# Etta_and_Gella_diamond_dev.net
KiCad netlist of a schematic drawn in EAGLE
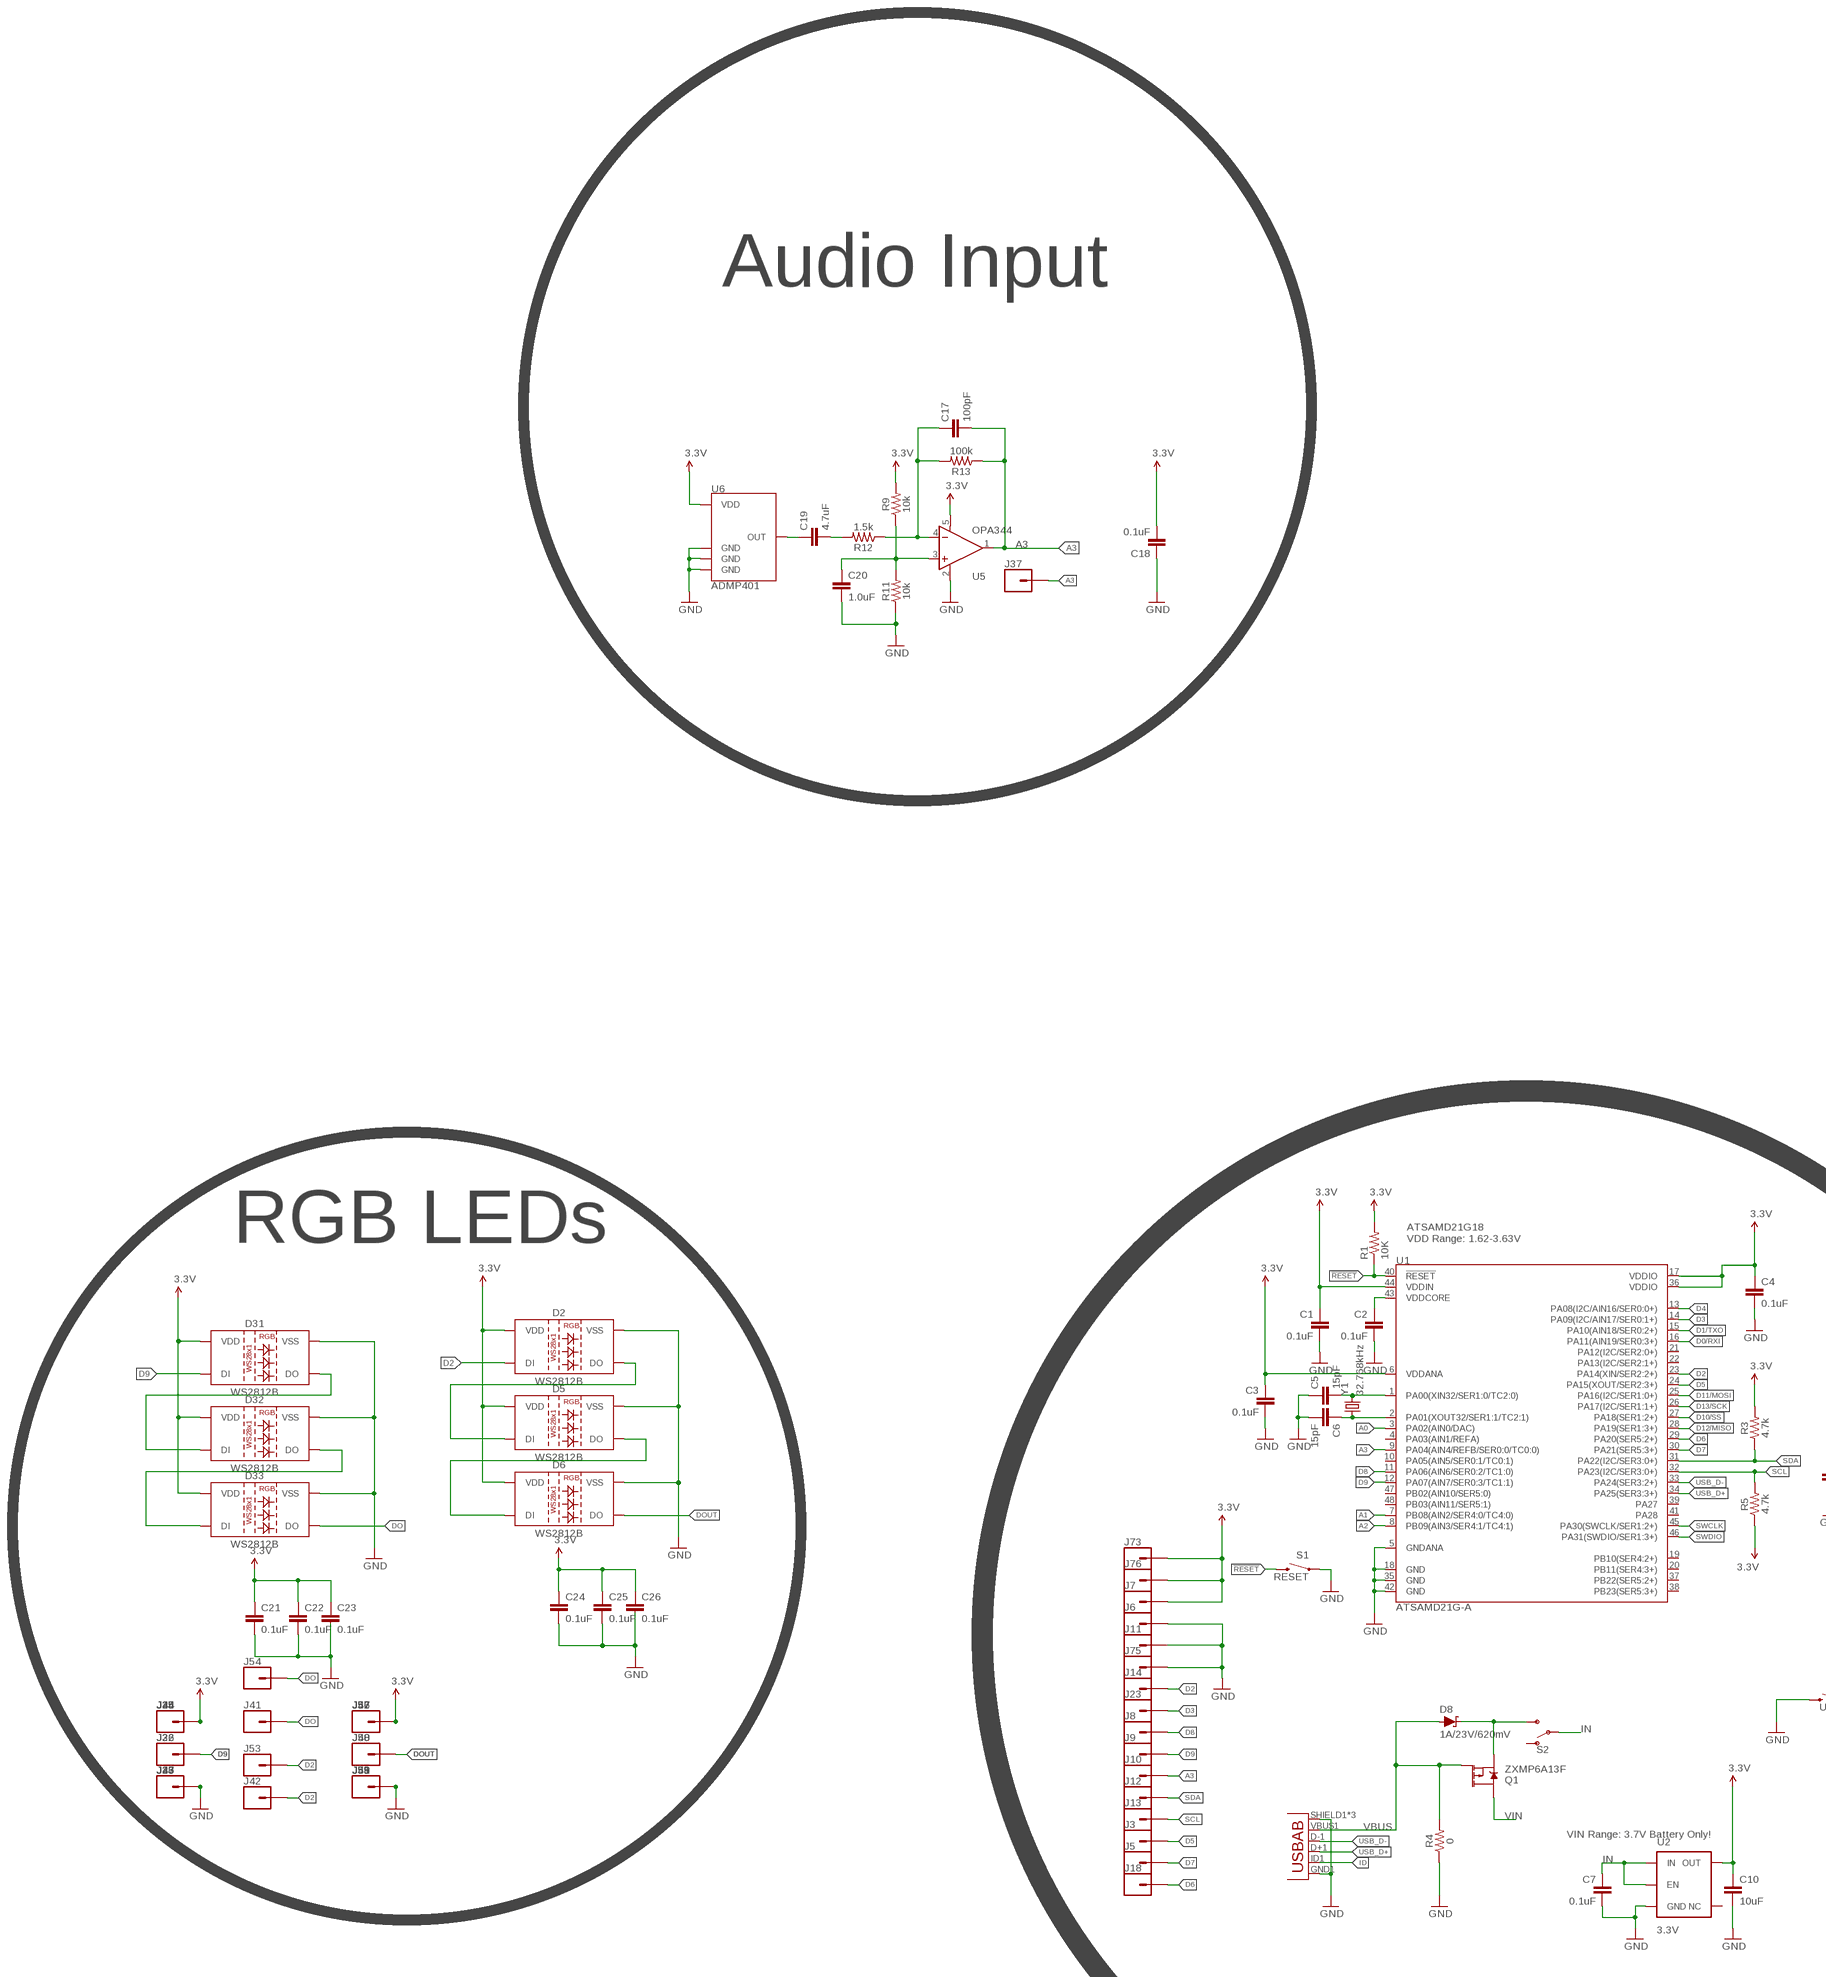
[diagram p0: schematic, sheet 1, part 1 of 3]
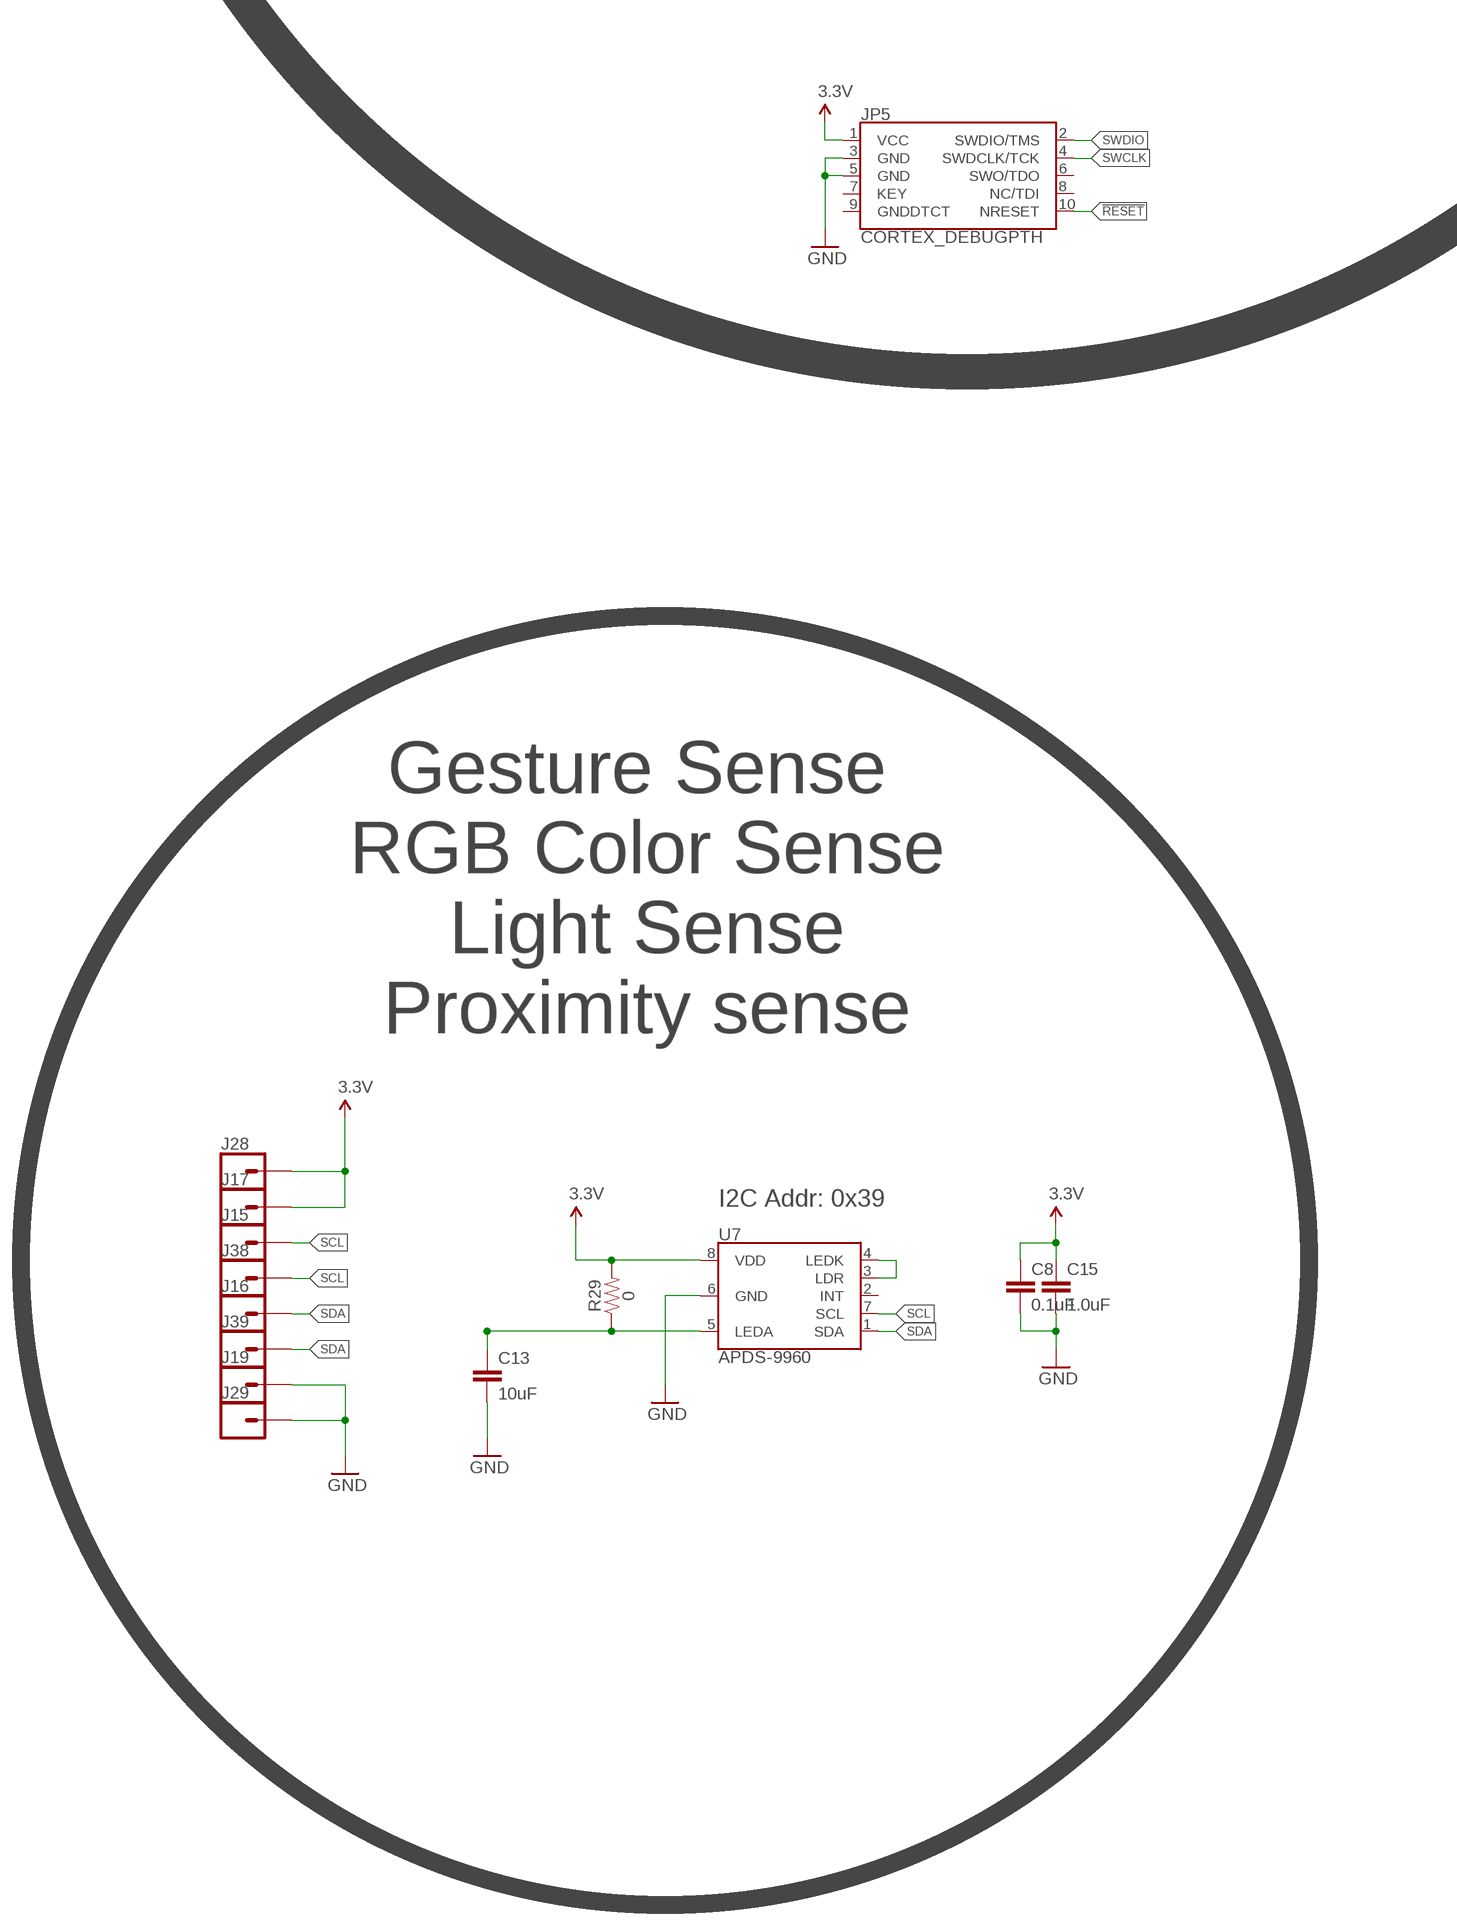
[diagram p1: schematic, sheet 1, part 2 of 3]
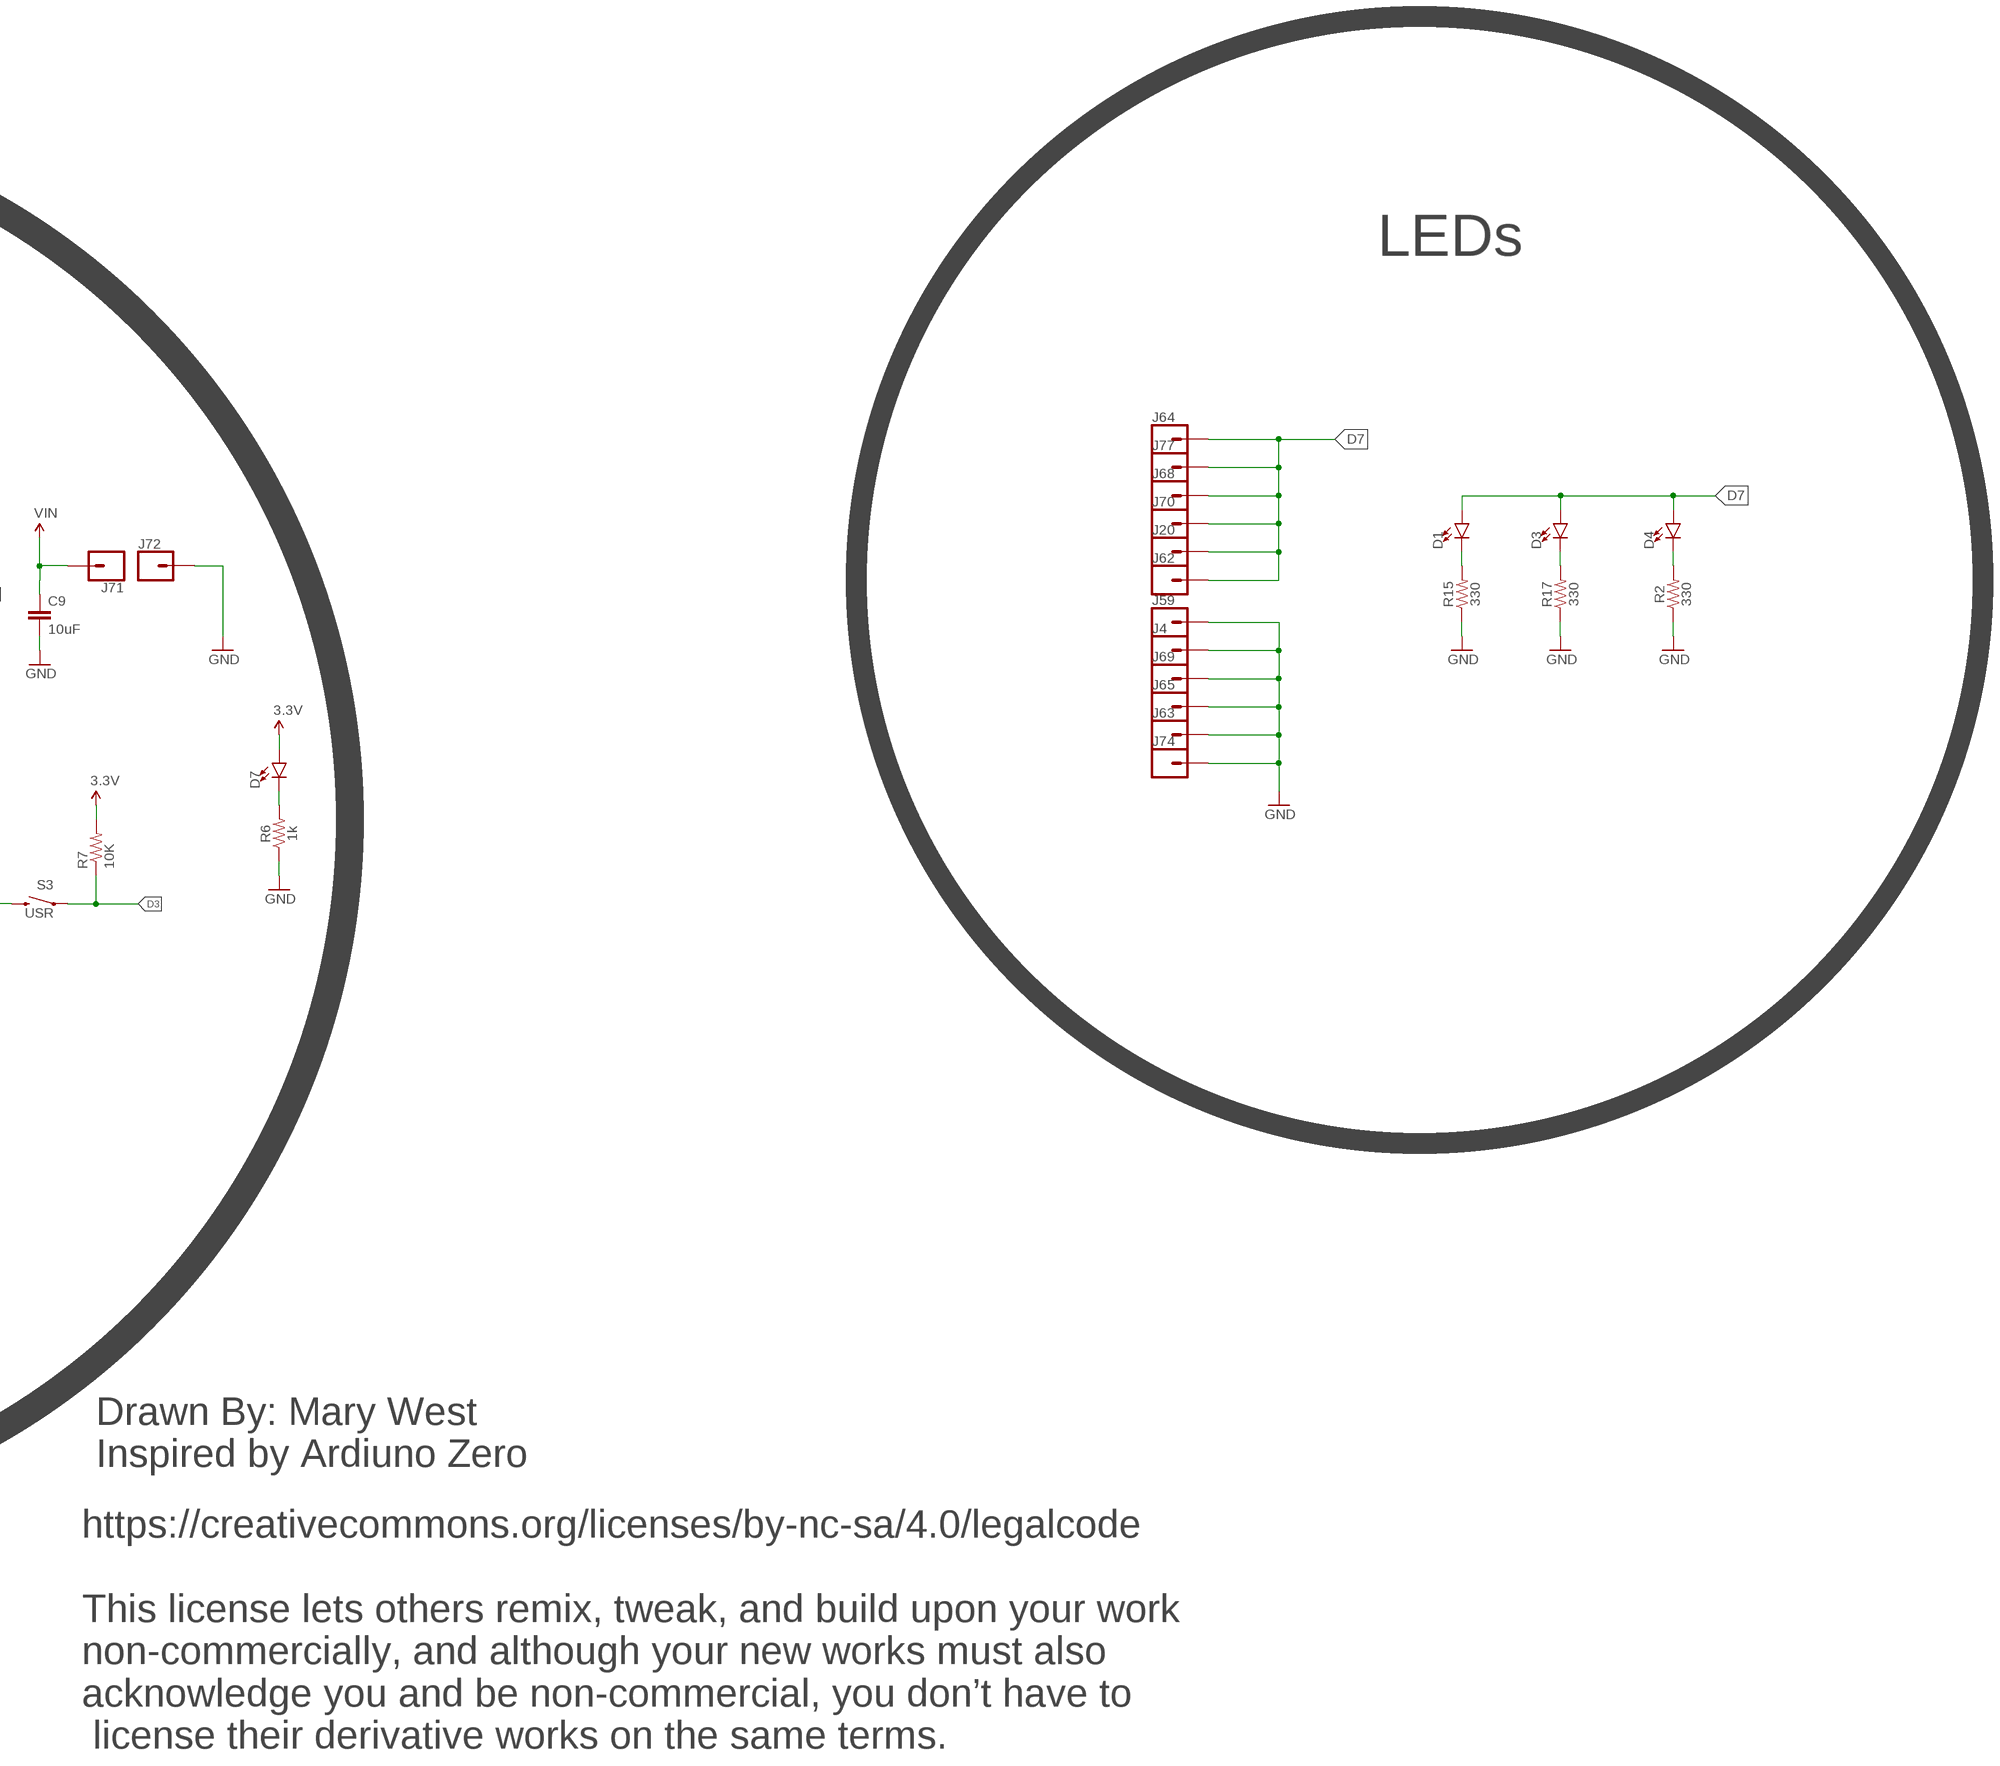
[diagram p2: schematic, sheet 1, part 3 of 3]

(export (version "E")
  (design (tool "Eeschema 10.0.6"))
  (components
    (comp (ref "C1")
      (value "0.1uF")
      (footprint "eagle-import:0603")
      (libsource (lib "eagle-import") (part "0.1UF-0603-25V-(+80/-20%)"))
    )
    (comp (ref "C2")
      (value "0.1uF")
      (footprint "eagle-import:0603")
      (libsource (lib "eagle-import") (part "0.1UF-0603-25V-(+80/-20%)"))
    )
    (comp (ref "C3")
      (value "0.1uF")
      (footprint "eagle-import:0603")
      (libsource (lib "eagle-import") (part "0.1UF-0603-25V-(+80/-20%)"))
    )
    (comp (ref "C4")
      (value "0.1uF")
      (footprint "eagle-import:0603")
      (libsource (lib "eagle-import") (part "0.1UF-0603-25V-(+80/-20%)"))
    )
    (comp (ref "C5")
      (value "15pF")
      (footprint "eagle-import:0603")
      (libsource (lib "eagle-import") (part "15PF-0603-50V-5%"))
    )
    (comp (ref "C6")
      (value "15pF")
      (footprint "eagle-import:0603")
      (libsource (lib "eagle-import") (part "15PF-0603-50V-5%"))
    )
    (comp (ref "C7")
      (value "0.1uF")
      (footprint "eagle-import:0603")
      (libsource (lib "eagle-import") (part "0.1UF-0603-25V-(+80/-20%)"))
    )
    (comp (ref "C8")
      (value "0.1uF")
      (footprint "eagle-import:0603")
      (libsource (lib "eagle-import") (part "0.1UF-0603-25V-(+80/-20%)"))
    )
    (comp (ref "C9")
      (value "10uF")
      (footprint "eagle-import:0603")
      (libsource (lib "eagle-import") (part "SparkFun-Capacitors_510_10UF-0603-6.3V-20%"))
    )
    (comp (ref "C10")
      (value "10uF")
      (footprint "eagle-import:0603")
      (libsource (lib "eagle-import") (part "SparkFun-Capacitors_510_10UF-0603-6.3V-20%"))
    )
    (comp (ref "C13")
      (value "10uF")
      (footprint "eagle-import:0805")
      (libsource (lib "eagle-import") (part "10UF-0805-10V-10%"))
    )
    (comp (ref "C15")
      (value "1.0uF")
      (footprint "eagle-import:0603")
      (libsource (lib "eagle-import") (part "1.0UF-0603-16V-10%"))
    )
    (comp (ref "C17")
      (value "100pF")
      (footprint "eagle-import:0603")
      (libsource (lib "eagle-import") (part "100PF-0603-50V-5%"))
    )
    (comp (ref "C18")
      (value "0.1uF")
      (footprint "eagle-import:0603")
      (libsource (lib "eagle-import") (part "0.1UF-0603-25V-(+80/-20%)"))
    )
    (comp (ref "C19")
      (value "4.7uF")
      (footprint "eagle-import:0603")
      (libsource (lib "eagle-import") (part "4.7UF-0603-6.3V-(10%)"))
    )
    (comp (ref "C20")
      (value "1.0uF")
      (footprint "eagle-import:0603")
      (libsource (lib "eagle-import") (part "1.0UF-0603-16V-10%"))
    )
    (comp (ref "C21")
      (value "0.1uF")
      (footprint "eagle-import:0603")
      (libsource (lib "eagle-import") (part "0.1UF-0603-25V-(+80/-20%)"))
    )
    (comp (ref "C22")
      (value "0.1uF")
      (footprint "eagle-import:0603")
      (libsource (lib "eagle-import") (part "0.1UF-0603-25V-(+80/-20%)"))
    )
    (comp (ref "C23")
      (value "0.1uF")
      (footprint "eagle-import:0603")
      (libsource (lib "eagle-import") (part "0.1UF-0603-25V-(+80/-20%)"))
    )
    (comp (ref "C24")
      (value "0.1uF")
      (footprint "eagle-import:0603")
      (libsource (lib "eagle-import") (part "0.1UF-0603-25V-(+80/-20%)"))
    )
    (comp (ref "C25")
      (value "0.1uF")
      (footprint "eagle-import:0603")
      (libsource (lib "eagle-import") (part "0.1UF-0603-25V-(+80/-20%)"))
    )
    (comp (ref "C26")
      (value "0.1uF")
      (footprint "eagle-import:0603")
      (libsource (lib "eagle-import") (part "0.1UF-0603-25V-(+80/-20%)"))
    )
    (comp (ref "D1")
      (value "LED1206")
      (footprint "eagle-import:LED-1206")
      (libsource (lib "eagle-import") (part "LED1206"))
    )
    (comp (ref "D2")
      (value "WS2812B")
      (footprint "eagle-import:WS2812B")
      (libsource (lib "eagle-import") (part "WS2812B"))
    )
    (comp (ref "D3")
      (value "LED1206")
      (footprint "eagle-import:LED-1206")
      (libsource (lib "eagle-import") (part "LED1206"))
    )
    (comp (ref "D4")
      (value "LED1206")
      (footprint "eagle-import:LED-1206")
      (libsource (lib "eagle-import") (part "LED1206"))
    )
    (comp (ref "D5")
      (value "WS2812B")
      (footprint "eagle-import:WS2812B")
      (libsource (lib "eagle-import") (part "WS2812B"))
    )
    (comp (ref "D6")
      (value "WS2812B")
      (footprint "eagle-import:WS2812B")
      (libsource (lib "eagle-import") (part "WS2812B"))
    )
    (comp (ref "D7")
      (value "LED1206")
      (footprint "eagle-import:LED-1206")
      (libsource (lib "eagle-import") (part "LED1206"))
    )
    (comp (ref "D8")
      (value "1A/23V/620mV")
      (footprint "eagle-import:SOD-323")
      (libsource (lib "eagle-import") (part "DIODE-SCHOTTKY-BAT20J"))
    )
    (comp (ref "D31")
      (value "WS2812B")
      (footprint "eagle-import:WS2812B")
      (libsource (lib "eagle-import") (part "WS2812B"))
    )
    (comp (ref "D32")
      (value "WS2812B")
      (footprint "eagle-import:WS2812B")
      (libsource (lib "eagle-import") (part "WS2812B"))
    )
    (comp (ref "D33")
      (value "WS2812B")
      (footprint "eagle-import:WS2812B")
      (libsource (lib "eagle-import") (part "WS2812B"))
    )
    (comp (ref "J3")
      (value "CONN_01")
      (footprint "eagle-import:1X01")
      (libsource (lib "eagle-import") (part "CONN_01"))
    )
    (comp (ref "J4")
      (value "CONN_01")
      (footprint "eagle-import:1X01")
      (libsource (lib "eagle-import") (part "CONN_01"))
    )
    (comp (ref "J5")
      (value "CONN_01")
      (footprint "eagle-import:1X01")
      (libsource (lib "eagle-import") (part "CONN_01"))
    )
    (comp (ref "J6")
      (value "CONN_01")
      (footprint "eagle-import:1X01")
      (libsource (lib "eagle-import") (part "CONN_01"))
    )
    (comp (ref "J7")
      (value "CONN_01")
      (footprint "eagle-import:1X01")
      (libsource (lib "eagle-import") (part "CONN_01"))
    )
    (comp (ref "J8")
      (value "CONN_01")
      (footprint "eagle-import:1X01")
      (libsource (lib "eagle-import") (part "CONN_01"))
    )
    (comp (ref "J9")
      (value "CONN_01")
      (footprint "eagle-import:1X01")
      (libsource (lib "eagle-import") (part "CONN_01"))
    )
    (comp (ref "J10")
      (value "CONN_01")
      (footprint "eagle-import:1X01")
      (libsource (lib "eagle-import") (part "CONN_01"))
    )
    (comp (ref "J11")
      (value "CONN_01")
      (footprint "eagle-import:1X01")
      (libsource (lib "eagle-import") (part "CONN_01"))
    )
    (comp (ref "J12")
      (value "CONN_01")
      (footprint "eagle-import:1X01")
      (libsource (lib "eagle-import") (part "CONN_01"))
    )
    (comp (ref "J13")
      (value "CONN_01")
      (footprint "eagle-import:1X01")
      (libsource (lib "eagle-import") (part "CONN_01"))
    )
    (comp (ref "J14")
      (value "CONN_01")
      (footprint "eagle-import:1X01")
      (libsource (lib "eagle-import") (part "CONN_01"))
    )
    (comp (ref "J15")
      (value "CONN_01")
      (footprint "eagle-import:1X01")
      (libsource (lib "eagle-import") (part "CONN_01"))
    )
    (comp (ref "J16")
      (value "CONN_01")
      (footprint "eagle-import:1X01")
      (libsource (lib "eagle-import") (part "CONN_01"))
    )
    (comp (ref "J17")
      (value "CONN_01")
      (footprint "eagle-import:1X01")
      (libsource (lib "eagle-import") (part "CONN_01"))
    )
    (comp (ref "J18")
      (value "CONN_01")
      (footprint "eagle-import:1X01")
      (libsource (lib "eagle-import") (part "CONN_01"))
    )
    (comp (ref "J19")
      (value "CONN_01")
      (footprint "eagle-import:1X01")
      (libsource (lib "eagle-import") (part "CONN_01"))
    )
    (comp (ref "J20")
      (value "CONN_01")
      (footprint "eagle-import:1X01")
      (libsource (lib "eagle-import") (part "CONN_01"))
    )
    (comp (ref "J23")
      (value "CONN_01")
      (footprint "eagle-import:1X01")
      (libsource (lib "eagle-import") (part "CONN_01"))
    )
    (comp (ref "J25")
      (value "CONN_01")
      (footprint "eagle-import:1X01")
      (libsource (lib "eagle-import") (part "CONN_01"))
    )
    (comp (ref "J26")
      (value "CONN_01")
      (footprint "eagle-import:1X01")
      (libsource (lib "eagle-import") (part "CONN_01"))
    )
    (comp (ref "J27")
      (value "CONN_01")
      (footprint "eagle-import:1X01")
      (libsource (lib "eagle-import") (part "CONN_01"))
    )
    (comp (ref "J28")
      (value "CONN_01")
      (footprint "eagle-import:1X01")
      (libsource (lib "eagle-import") (part "CONN_01"))
    )
    (comp (ref "J29")
      (value "CONN_01")
      (footprint "eagle-import:1X01")
      (libsource (lib "eagle-import") (part "CONN_01"))
    )
    (comp (ref "J32")
      (value "CONN_01")
      (footprint "eagle-import:1X01")
      (libsource (lib "eagle-import") (part "CONN_01"))
    )
    (comp (ref "J33")
      (value "CONN_01")
      (footprint "eagle-import:1X01")
      (libsource (lib "eagle-import") (part "CONN_01"))
    )
    (comp (ref "J34")
      (value "CONN_01")
      (footprint "eagle-import:1X01")
      (libsource (lib "eagle-import") (part "CONN_01"))
    )
    (comp (ref "J37")
      (value "CONN_01")
      (footprint "eagle-import:1X01")
      (libsource (lib "eagle-import") (part "CONN_01"))
    )
    (comp (ref "J38")
      (value "CONN_01")
      (footprint "eagle-import:1X01")
      (libsource (lib "eagle-import") (part "CONN_01"))
    )
    (comp (ref "J39")
      (value "CONN_01")
      (footprint "eagle-import:1X01")
      (libsource (lib "eagle-import") (part "CONN_01"))
    )
    (comp (ref "J41")
      (value "CONN_01")
      (footprint "eagle-import:1X01")
      (libsource (lib "eagle-import") (part "CONN_01"))
    )
    (comp (ref "J42")
      (value "CONN_01")
      (footprint "eagle-import:1X01")
      (libsource (lib "eagle-import") (part "CONN_01"))
    )
    (comp (ref "J43")
      (value "CONN_01")
      (footprint "eagle-import:1X01")
      (libsource (lib "eagle-import") (part "CONN_01"))
    )
    (comp (ref "J44")
      (value "CONN_01")
      (footprint "eagle-import:1X01")
      (libsource (lib "eagle-import") (part "CONN_01"))
    )
    (comp (ref "J45")
      (value "CONN_01")
      (footprint "eagle-import:1X01")
      (libsource (lib "eagle-import") (part "CONN_01"))
    )
    (comp (ref "J46")
      (value "CONN_01")
      (footprint "eagle-import:1X01")
      (libsource (lib "eagle-import") (part "CONN_01"))
    )
    (comp (ref "J47")
      (value "CONN_01")
      (footprint "eagle-import:1X01")
      (libsource (lib "eagle-import") (part "CONN_01"))
    )
    (comp (ref "J48")
      (value "CONN_01")
      (footprint "eagle-import:1X01")
      (libsource (lib "eagle-import") (part "CONN_01"))
    )
    (comp (ref "J49")
      (value "CONN_01")
      (footprint "eagle-import:1X01")
      (libsource (lib "eagle-import") (part "CONN_01"))
    )
    (comp (ref "J50")
      (value "CONN_01")
      (footprint "eagle-import:1X01")
      (libsource (lib "eagle-import") (part "CONN_01"))
    )
    (comp (ref "J51")
      (value "CONN_01")
      (footprint "eagle-import:1X01")
      (libsource (lib "eagle-import") (part "CONN_01"))
    )
    (comp (ref "J52")
      (value "CONN_01")
      (footprint "eagle-import:1X01")
      (libsource (lib "eagle-import") (part "CONN_01"))
    )
    (comp (ref "J53")
      (value "CONN_01")
      (footprint "eagle-import:1X01")
      (libsource (lib "eagle-import") (part "CONN_01"))
    )
    (comp (ref "J54")
      (value "CONN_01")
      (footprint "eagle-import:1X01")
      (libsource (lib "eagle-import") (part "CONN_01"))
    )
    (comp (ref "J55")
      (value "CONN_01")
      (footprint "eagle-import:1X01")
      (libsource (lib "eagle-import") (part "CONN_01"))
    )
    (comp (ref "J56")
      (value "CONN_01")
      (footprint "eagle-import:1X01")
      (libsource (lib "eagle-import") (part "CONN_01"))
    )
    (comp (ref "J57")
      (value "CONN_01")
      (footprint "eagle-import:1X01")
      (libsource (lib "eagle-import") (part "CONN_01"))
    )
    (comp (ref "J58")
      (value "CONN_01")
      (footprint "eagle-import:1X01")
      (libsource (lib "eagle-import") (part "CONN_01"))
    )
    (comp (ref "J59")
      (value "CONN_01")
      (footprint "eagle-import:1X01")
      (libsource (lib "eagle-import") (part "CONN_01"))
    )
    (comp (ref "J62")
      (value "CONN_01")
      (footprint "eagle-import:1X01")
      (libsource (lib "eagle-import") (part "CONN_01"))
    )
    (comp (ref "J63")
      (value "CONN_01")
      (footprint "eagle-import:1X01")
      (libsource (lib "eagle-import") (part "CONN_01"))
    )
    (comp (ref "J64")
      (value "CONN_01")
      (footprint "eagle-import:1X01")
      (libsource (lib "eagle-import") (part "CONN_01"))
    )
    (comp (ref "J65")
      (value "CONN_01")
      (footprint "eagle-import:1X01")
      (libsource (lib "eagle-import") (part "CONN_01"))
    )
    (comp (ref "J68")
      (value "CONN_01")
      (footprint "eagle-import:1X01")
      (libsource (lib "eagle-import") (part "CONN_01"))
    )
    (comp (ref "J69")
      (value "CONN_01")
      (footprint "eagle-import:1X01")
      (libsource (lib "eagle-import") (part "CONN_01"))
    )
    (comp (ref "J70")
      (value "CONN_01")
      (footprint "eagle-import:1X01")
      (libsource (lib "eagle-import") (part "CONN_01"))
    )
    (comp (ref "J71")
      (value "CONN_01")
      (footprint "eagle-import:1X01")
      (libsource (lib "eagle-import") (part "CONN_01"))
    )
    (comp (ref "J72")
      (value "CONN_01")
      (footprint "eagle-import:1X01")
      (libsource (lib "eagle-import") (part "CONN_01"))
    )
    (comp (ref "J73")
      (value "CONN_01")
      (footprint "eagle-import:1X01")
      (libsource (lib "eagle-import") (part "CONN_01"))
    )
    (comp (ref "J74")
      (value "CONN_01")
      (footprint "eagle-import:1X01")
      (libsource (lib "eagle-import") (part "CONN_01"))
    )
    (comp (ref "J75")
      (value "CONN_01")
      (footprint "eagle-import:1X01")
      (libsource (lib "eagle-import") (part "CONN_01"))
    )
    (comp (ref "J76")
      (value "CONN_01")
      (footprint "eagle-import:1X01")
      (libsource (lib "eagle-import") (part "CONN_01"))
    )
    (comp (ref "J77")
      (value "CONN_01")
      (footprint "eagle-import:1X01")
      (libsource (lib "eagle-import") (part "CONN_01"))
    )
    (comp (ref "JP3")
      (value "USB-ABCONN-11794")
      (footprint "eagle-import:USB-AB-MICRO-SMD_V03")
      (libsource (lib "eagle-import") (part "USB-ABCONN-11794"))
    )
    (comp (ref "JP5")
      (value "CORTEX_DEBUGPTH")
      (footprint "eagle-import:2X5-PTH-1.27MM")
      (libsource (lib "eagle-import") (part "CORTEX_DEBUGPTH"))
    )
    (comp (ref "Q1")
      (value "ZXMP6A13F")
      (footprint "eagle-import:SOT23-3")
      (libsource (lib "eagle-import") (part "MOSFET_PCH-SI2309DS"))
    )
    (comp (ref "R1")
      (value "10K")
      (footprint "eagle-import:0603-RES@1")
      (libsource (lib "eagle-import") (part "10KOHM-1/10W-1%(0603)0603"))
    )
    (comp (ref "R2")
      (value "330")
      (footprint "eagle-import:0603")
      (libsource (lib "eagle-import") (part "330OHM-0603-1/10W-1%"))
    )
    (comp (ref "R3")
      (value "4.7k")
      (footprint "eagle-import:0603")
      (libsource (lib "eagle-import") (part "4.7KOHM-0603-1/10W-1%"))
    )
    (comp (ref "R4")
      (value "0")
      (footprint "eagle-import:0603")
      (libsource (lib "eagle-import") (part "0OHM-0603-1/10W-5%"))
    )
    (comp (ref "R5")
      (value "4.7k")
      (footprint "eagle-import:0603")
      (libsource (lib "eagle-import") (part "4.7KOHM-0603-1/10W-1%"))
    )
    (comp (ref "R6")
      (value "1k")
      (footprint "eagle-import:0603")
      (libsource (lib "eagle-import") (part "330OHM-0603-1/10W-1%"))
    )
    (comp (ref "R7")
      (value "10K")
      (footprint "eagle-import:0603-RES@1")
      (libsource (lib "eagle-import") (part "10KOHM-1/10W-1%(0603)0603"))
    )
    (comp (ref "R9")
      (value "10k")
      (footprint "eagle-import:0603")
      (libsource (lib "eagle-import") (part "10KOHM-0603-1/10W-1%"))
    )
    (comp (ref "R11")
      (value "10k")
      (footprint "eagle-import:0603")
      (libsource (lib "eagle-import") (part "10KOHM-0603-1/10W-1%"))
    )
    (comp (ref "R12")
      (value "1.5k")
      (footprint "eagle-import:0603")
      (libsource (lib "eagle-import") (part "1.5KOHM-0603-1/10W-1%"))
    )
    (comp (ref "R13")
      (value "100k")
      (footprint "eagle-import:0603")
      (libsource (lib "eagle-import") (part "100KOHM-0603-1/10W-1%"))
    )
    (comp (ref "R15")
      (value "330")
      (footprint "eagle-import:0603")
      (libsource (lib "eagle-import") (part "330OHM-0603-1/10W-1%"))
    )
    (comp (ref "R17")
      (value "330")
      (footprint "eagle-import:0603")
      (libsource (lib "eagle-import") (part "330OHM-0603-1/10W-1%"))
    )
    (comp (ref "R29")
      (value "0")
      (footprint "eagle-import:0603")
      (libsource (lib "eagle-import") (part "0OHM-0603-1/10W-5%"))
    )
    (comp (ref "S1")
      (value "RESET")
      (footprint "eagle-import:TACTILE_SWITCH_SMD_4.6X2.8MM")
      (libsource (lib "eagle-import") (part "SWITCH-MOMENTARY-2SMD-4.6X2.8MM"))
    )
    (comp (ref "S2")
      (value "SWITCH-SPDT-SMD-AYZ0202")
      (footprint "eagle-import:SWITCH_DPDT_SMD_AYZ0202")
      (libsource (lib "eagle-import") (part "SWITCH-SPDT-SMD-AYZ0202"))
    )
    (comp (ref "S3")
      (value "USR")
      (footprint "eagle-import:TACTILE_SWITCH_SMD_4.6X2.8MM")
      (libsource (lib "eagle-import") (part "SWITCH-MOMENTARY-2SMD-4.6X2.8MM"))
    )
    (comp (ref "U1")
      (value "ATSAMD21G-A")
      (footprint "eagle-import:TQFP-48")
      (libsource (lib "eagle-import") (part "ATSAMD21G-A"))
    )
    (comp (ref "U2")
      (value "3.3V")
      (footprint "eagle-import:SOT23-5")
      (libsource (lib "eagle-import") (part "V_REG_AP2112K-3.3V"))
    )
    (comp (ref "U5")
      (value "OPA344")
      (footprint "eagle-import:SOT23-5")
      (libsource (lib "eagle-import") (part "OPA344"))
    )
    (comp (ref "U6")
      (value "ADMP401")
      (footprint "eagle-import:ADMP401")
      (libsource (lib "eagle-import") (part "ADMP401"))
    )
    (comp (ref "U7")
      (value "APDS-9960")
      (footprint "eagle-import:APDS-9960")
      (libsource (lib "eagle-import") (part "APDS-9960"))
    )
    (comp (ref "Y1")
      (value "32.768kHz")
      (footprint "eagle-import:CRYSTAL-SMD-3.2X1.5MM")
      (libsource (lib "eagle-import") (part "CRYSTAL3.2X1.5MM"))
    )
  )
  (nets
    (net (code "1") (name "/IN") (class "Default")
      (node (ref "C7") (pin "1") (pinfunction "1_1") (pintype "passive"))
      (node (ref "S2") (pin "2") (pinfunction "P_2") (pintype "passive"))
      (node (ref "U2") (pin "1") (pinfunction "IN_1") (pintype "input"))
      (node (ref "U2") (pin "3") (pinfunction "EN_3") (pintype "input"))
    )
    (net (code "2") (name "/VBUS") (class "Default")
      (node (ref "D8") (pin "A") (pinfunction "A_A") (pintype "passive"))
      (node (ref "JP3") (pin "VBUS1") (pinfunction "VBUS_VBUS1") (pintype "bidirectional"))
      (node (ref "Q1") (pin "1") (pinfunction "G_1") (pintype "bidirectional"))
      (node (ref "R4") (pin "2") (pinfunction "2_2") (pintype "passive"))
    )
    (net (code "3") (name "/~{RESET}") (class "Default")
      (node (ref "JP5") (pin "10") (pinfunction "NRESET_10") (pintype "bidirectional"))
      (node (ref "R1") (pin "1") (pinfunction "1_1") (pintype "passive"))
      (node (ref "S1") (pin "3") (pinfunction "2_3") (pintype "passive"))
      (node (ref "S1") (pin "4") (pinfunction "2_4") (pintype "passive"))
      (node (ref "U1") (pin "40") (pinfunction "~{RESET}_40") (pintype "bidirectional"))
    )
    (net (code "4") (name "3.3V") (class "Default")
      (node (ref "C1") (pin "1") (pinfunction "1_1") (pintype "passive"))
      (node (ref "C10") (pin "1") (pinfunction "1_1") (pintype "passive"))
      (node (ref "C15") (pin "1") (pinfunction "1_1") (pintype "passive"))
      (node (ref "C18") (pin "2") (pinfunction "2_2") (pintype "passive"))
      (node (ref "C21") (pin "1") (pinfunction "1_1") (pintype "passive"))
      (node (ref "C22") (pin "1") (pinfunction "1_1") (pintype "passive"))
      (node (ref "C23") (pin "1") (pinfunction "1_1") (pintype "passive"))
      (node (ref "C24") (pin "1") (pinfunction "1_1") (pintype "passive"))
      (node (ref "C25") (pin "1") (pinfunction "1_1") (pintype "passive"))
      (node (ref "C26") (pin "1") (pinfunction "1_1") (pintype "passive"))
      (node (ref "C3") (pin "1") (pinfunction "1_1") (pintype "passive"))
      (node (ref "C4") (pin "1") (pinfunction "1_1") (pintype "passive"))
      (node (ref "C8") (pin "1") (pinfunction "1_1") (pintype "passive"))
      (node (ref "D2") (pin "1") (pinfunction "VDD_1") (pintype "bidirectional"))
      (node (ref "D31") (pin "1") (pinfunction "VDD_1") (pintype "bidirectional"))
      (node (ref "D32") (pin "1") (pinfunction "VDD_1") (pintype "bidirectional"))
      (node (ref "D33") (pin "1") (pinfunction "VDD_1") (pintype "bidirectional"))
      (node (ref "D5") (pin "1") (pinfunction "VDD_1") (pintype "bidirectional"))
      (node (ref "D6") (pin "1") (pinfunction "VDD_1") (pintype "bidirectional"))
      (node (ref "D7") (pin "A") (pinfunction "A_A") (pintype "passive"))
      (node (ref "J17") (pin "P$1") (pinfunction "1_P$1") (pintype "passive"))
      (node (ref "J25") (pin "P$1") (pinfunction "1_P$1") (pintype "passive"))
      (node (ref "J28") (pin "P$1") (pinfunction "1_P$1") (pintype "passive"))
      (node (ref "J34") (pin "P$1") (pinfunction "1_P$1") (pintype "passive"))
      (node (ref "J44") (pin "P$1") (pinfunction "1_P$1") (pintype "passive"))
      (node (ref "J45") (pin "P$1") (pinfunction "1_P$1") (pintype "passive"))
      (node (ref "J47") (pin "P$1") (pinfunction "1_P$1") (pintype "passive"))
      (node (ref "J52") (pin "P$1") (pinfunction "1_P$1") (pintype "passive"))
      (node (ref "J56") (pin "P$1") (pinfunction "1_P$1") (pintype "passive"))
      (node (ref "J57") (pin "P$1") (pinfunction "1_P$1") (pintype "passive"))
      (node (ref "J7") (pin "P$1") (pinfunction "1_P$1") (pintype "passive"))
      (node (ref "J73") (pin "P$1") (pinfunction "1_P$1") (pintype "passive"))
      (node (ref "J76") (pin "P$1") (pinfunction "1_P$1") (pintype "passive"))
      (node (ref "JP5") (pin "1") (pinfunction "VCC_1") (pintype "bidirectional"))
      (node (ref "R1") (pin "2") (pinfunction "2_2") (pintype "passive"))
      (node (ref "R29") (pin "2") (pinfunction "2_2") (pintype "passive"))
      (node (ref "R3") (pin "2") (pinfunction "2_2") (pintype "passive"))
      (node (ref "R5") (pin "1") (pinfunction "1_1") (pintype "passive"))
      (node (ref "R7") (pin "2") (pinfunction "2_2") (pintype "passive"))
      (node (ref "R9") (pin "2") (pinfunction "2_2") (pintype "passive"))
      (node (ref "U1") (pin "17") (pinfunction "VDDIO_17") (pintype "bidirectional"))
      (node (ref "U1") (pin "36") (pinfunction "VDDIO_36") (pintype "bidirectional"))
      (node (ref "U1") (pin "44") (pinfunction "VDDIN_44") (pintype "bidirectional"))
      (node (ref "U1") (pin "6") (pinfunction "VDDANA_6") (pintype "bidirectional"))
      (node (ref "U2") (pin "5") (pinfunction "OUT_5") (pintype "passive"))
      (node (ref "U5") (pin "5") (pinfunction "V+_5") (pintype "power_in"))
      (node (ref "U6") (pin "5") (pinfunction "VDD_5") (pintype "bidirectional"))
      (node (ref "U7") (pin "8") (pinfunction "VDD_8") (pintype "bidirectional"))
    )
    (net (code "5") (name "A0") (class "Default")
      (node (ref "U1") (pin "3") (pinfunction "PA02(AIN0/DAC)_3") (pintype "bidirectional"))
    )
    (net (code "6") (name "A1") (class "Default")
      (node (ref "U1") (pin "7") (pinfunction "PB08(AIN2/SER4:0/TC4:0)_7") (pintype "bidirectional"))
    )
    (net (code "7") (name "A2") (class "Default")
      (node (ref "U1") (pin "8") (pinfunction "PB09(AIN3/SER4:1/TC4:1)_8") (pintype "bidirectional"))
    )
    (net (code "8") (name "A3") (class "Default")
      (node (ref "C17") (pin "2") (pinfunction "2_2") (pintype "passive"))
      (node (ref "J10") (pin "P$1") (pinfunction "1_P$1") (pintype "passive"))
      (node (ref "J37") (pin "P$1") (pinfunction "1_P$1") (pintype "passive"))
      (node (ref "R13") (pin "1") (pinfunction "1_1") (pintype "passive"))
      (node (ref "U1") (pin "9") (pinfunction "PA04(AIN4/REFB/SER0:0/TC0:0)_9") (pintype "bidirectional"))
      (node (ref "U5") (pin "1") (pinfunction "OUT_1") (pintype "output"))
    )
    (net (code "9") (name "D0{slash}RXI") (class "Default")
      (node (ref "U1") (pin "16") (pinfunction "PA11(AIN19/SER0:3+)_16") (pintype "bidirectional"))
    )
    (net (code "10") (name "D1{slash}TXO") (class "Default")
      (node (ref "U1") (pin "15") (pinfunction "PA10(AIN18/SER0:2+)_15") (pintype "bidirectional"))
    )
    (net (code "11") (name "D2") (class "Default")
      (node (ref "D2") (pin "4") (pinfunction "DI_4") (pintype "bidirectional"))
      (node (ref "J14") (pin "P$1") (pinfunction "1_P$1") (pintype "passive"))
      (node (ref "J42") (pin "P$1") (pinfunction "1_P$1") (pintype "passive"))
      (node (ref "J53") (pin "P$1") (pinfunction "1_P$1") (pintype "passive"))
      (node (ref "U1") (pin "23") (pinfunction "PA14(XIN/SER2:2+)_23") (pintype "bidirectional"))
    )
    (net (code "12") (name "D3") (class "Default")
      (node (ref "J23") (pin "P$1") (pinfunction "1_P$1") (pintype "passive"))
      (node (ref "R7") (pin "1") (pinfunction "1_1") (pintype "passive"))
      (node (ref "S3") (pin "1") (pinfunction "1_1") (pintype "passive"))
      (node (ref "S3") (pin "2") (pinfunction "1_2") (pintype "passive"))
      (node (ref "U1") (pin "14") (pinfunction "PA09(I2C/AIN17/SER0:1+)_14") (pintype "bidirectional"))
    )
    (net (code "13") (name "D4") (class "Default")
      (node (ref "U1") (pin "13") (pinfunction "PA08(I2C/AIN16/SER0:0+)_13") (pintype "bidirectional"))
    )
    (net (code "14") (name "D5") (class "Default")
      (node (ref "J3") (pin "P$1") (pinfunction "1_P$1") (pintype "passive"))
      (node (ref "U1") (pin "24") (pinfunction "PA15(XOUT/SER2:3+)_24") (pintype "bidirectional"))
    )
    (net (code "15") (name "D6") (class "Default")
      (node (ref "J18") (pin "P$1") (pinfunction "1_P$1") (pintype "passive"))
      (node (ref "U1") (pin "29") (pinfunction "PA20(SER5:2+)_29") (pintype "bidirectional"))
    )
    (net (code "16") (name "D7") (class "Default")
      (node (ref "D1") (pin "A") (pinfunction "A_A") (pintype "passive"))
      (node (ref "D3") (pin "A") (pinfunction "A_A") (pintype "passive"))
      (node (ref "D4") (pin "A") (pinfunction "A_A") (pintype "passive"))
      (node (ref "J20") (pin "P$1") (pinfunction "1_P$1") (pintype "passive"))
      (node (ref "J5") (pin "P$1") (pinfunction "1_P$1") (pintype "passive"))
      (node (ref "J62") (pin "P$1") (pinfunction "1_P$1") (pintype "passive"))
      (node (ref "J64") (pin "P$1") (pinfunction "1_P$1") (pintype "passive"))
      (node (ref "J68") (pin "P$1") (pinfunction "1_P$1") (pintype "passive"))
      (node (ref "J70") (pin "P$1") (pinfunction "1_P$1") (pintype "passive"))
      (node (ref "J77") (pin "P$1") (pinfunction "1_P$1") (pintype "passive"))
      (node (ref "U1") (pin "30") (pinfunction "PA21(SER5:3+)_30") (pintype "bidirectional"))
    )
    (net (code "17") (name "D8") (class "Default")
      (node (ref "J8") (pin "P$1") (pinfunction "1_P$1") (pintype "passive"))
      (node (ref "U1") (pin "11") (pinfunction "PA06(AIN6/SER0:2/TC1:0)_11") (pintype "bidirectional"))
    )
    (net (code "18") (name "D9") (class "Default")
      (node (ref "D31") (pin "4") (pinfunction "DI_4") (pintype "bidirectional"))
      (node (ref "J26") (pin "P$1") (pinfunction "1_P$1") (pintype "passive"))
      (node (ref "J32") (pin "P$1") (pinfunction "1_P$1") (pintype "passive"))
      (node (ref "J9") (pin "P$1") (pinfunction "1_P$1") (pintype "passive"))
      (node (ref "U1") (pin "12") (pinfunction "PA07(AIN7/SER0:3/TC1:1)_12") (pintype "bidirectional"))
    )
    (net (code "19") (name "D10{slash}SS") (class "Default")
      (node (ref "U1") (pin "27") (pinfunction "PA18(SER1:2+)_27") (pintype "bidirectional"))
    )
    (net (code "20") (name "D11{slash}MOSI") (class "Default")
      (node (ref "U1") (pin "25") (pinfunction "PA16(I2C/SER1:0+)_25") (pintype "bidirectional"))
    )
    (net (code "21") (name "D12{slash}MISO") (class "Default")
      (node (ref "U1") (pin "28") (pinfunction "PA19(SER1:3+)_28") (pintype "bidirectional"))
    )
    (net (code "22") (name "D13{slash}SCK") (class "Default")
      (node (ref "U1") (pin "26") (pinfunction "PA17(I2C/SER1:1+)_26") (pintype "bidirectional"))
    )
    (net (code "23") (name "DO") (class "Default")
      (node (ref "D33") (pin "2") (pinfunction "DO_2") (pintype "bidirectional"))
      (node (ref "J41") (pin "P$1") (pinfunction "1_P$1") (pintype "passive"))
      (node (ref "J54") (pin "P$1") (pinfunction "1_P$1") (pintype "passive"))
    )
    (net (code "24") (name "DOUT") (class "Default")
      (node (ref "D6") (pin "2") (pinfunction "DO_2") (pintype "bidirectional"))
      (node (ref "J48") (pin "P$1") (pinfunction "1_P$1") (pintype "passive"))
      (node (ref "J50") (pin "P$1") (pinfunction "1_P$1") (pintype "passive"))
    )
    (net (code "25") (name "GND") (class "Default")
      (node (ref "C1") (pin "2") (pinfunction "2_2") (pintype "passive"))
      (node (ref "C10") (pin "2") (pinfunction "2_2") (pintype "passive"))
      (node (ref "C13") (pin "2") (pinfunction "2_2") (pintype "passive"))
      (node (ref "C15") (pin "2") (pinfunction "2_2") (pintype "passive"))
      (node (ref "C18") (pin "1") (pinfunction "1_1") (pintype "passive"))
      (node (ref "C2") (pin "2") (pinfunction "2_2") (pintype "passive"))
      (node (ref "C20") (pin "2") (pinfunction "2_2") (pintype "passive"))
      (node (ref "C21") (pin "2") (pinfunction "2_2") (pintype "passive"))
      (node (ref "C22") (pin "2") (pinfunction "2_2") (pintype "passive"))
      (node (ref "C23") (pin "2") (pinfunction "2_2") (pintype "passive"))
      (node (ref "C24") (pin "2") (pinfunction "2_2") (pintype "passive"))
      (node (ref "C25") (pin "2") (pinfunction "2_2") (pintype "passive"))
      (node (ref "C26") (pin "2") (pinfunction "2_2") (pintype "passive"))
      (node (ref "C3") (pin "2") (pinfunction "2_2") (pintype "passive"))
      (node (ref "C4") (pin "2") (pinfunction "2_2") (pintype "passive"))
      (node (ref "C5") (pin "1") (pinfunction "1_1") (pintype "passive"))
      (node (ref "C6") (pin "2") (pinfunction "2_2") (pintype "passive"))
      (node (ref "C7") (pin "2") (pinfunction "2_2") (pintype "passive"))
      (node (ref "C8") (pin "2") (pinfunction "2_2") (pintype "passive"))
      (node (ref "C9") (pin "2") (pinfunction "2_2") (pintype "passive"))
      (node (ref "D2") (pin "3") (pinfunction "VSS_3") (pintype "bidirectional"))
      (node (ref "D31") (pin "3") (pinfunction "VSS_3") (pintype "bidirectional"))
      (node (ref "D32") (pin "3") (pinfunction "VSS_3") (pintype "bidirectional"))
      (node (ref "D33") (pin "3") (pinfunction "VSS_3") (pintype "bidirectional"))
      (node (ref "D5") (pin "3") (pinfunction "VSS_3") (pintype "bidirectional"))
      (node (ref "D6") (pin "3") (pinfunction "VSS_3") (pintype "bidirectional"))
      (node (ref "J11") (pin "P$1") (pinfunction "1_P$1") (pintype "passive"))
      (node (ref "J19") (pin "P$1") (pinfunction "1_P$1") (pintype "passive"))
      (node (ref "J27") (pin "P$1") (pinfunction "1_P$1") (pintype "passive"))
      (node (ref "J29") (pin "P$1") (pinfunction "1_P$1") (pintype "passive"))
      (node (ref "J33") (pin "P$1") (pinfunction "1_P$1") (pintype "passive"))
      (node (ref "J4") (pin "P$1") (pinfunction "1_P$1") (pintype "passive"))
      (node (ref "J43") (pin "P$1") (pinfunction "1_P$1") (pintype "passive"))
      (node (ref "J46") (pin "P$1") (pinfunction "1_P$1") (pintype "passive"))
      (node (ref "J49") (pin "P$1") (pinfunction "1_P$1") (pintype "passive"))
      (node (ref "J51") (pin "P$1") (pinfunction "1_P$1") (pintype "passive"))
      (node (ref "J55") (pin "P$1") (pinfunction "1_P$1") (pintype "passive"))
      (node (ref "J58") (pin "P$1") (pinfunction "1_P$1") (pintype "passive"))
      (node (ref "J59") (pin "P$1") (pinfunction "1_P$1") (pintype "passive"))
      (node (ref "J6") (pin "P$1") (pinfunction "1_P$1") (pintype "passive"))
      (node (ref "J63") (pin "P$1") (pinfunction "1_P$1") (pintype "passive"))
      (node (ref "J65") (pin "P$1") (pinfunction "1_P$1") (pintype "passive"))
      (node (ref "J69") (pin "P$1") (pinfunction "1_P$1") (pintype "passive"))
      (node (ref "J72") (pin "P$1") (pinfunction "1_P$1") (pintype "passive"))
      (node (ref "J74") (pin "P$1") (pinfunction "1_P$1") (pintype "passive"))
      (node (ref "J75") (pin "P$1") (pinfunction "1_P$1") (pintype "passive"))
      (node (ref "JP3") (pin "GND1") (pinfunction "GND_GND1") (pintype "bidirectional"))
      (node (ref "JP3") (pin "SHIELD1") (pinfunction "SHIELD_SHIELD1") (pintype "bidirectional"))
      (node (ref "JP3") (pin "SHIELD2") (pinfunction "SHIELD_SHIELD2") (pintype "bidirectional"))
      (node (ref "JP3") (pin "SHIELD3") (pinfunction "SHIELD_SHIELD3") (pintype "bidirectional"))
      (node (ref "JP5") (pin "3") (pinfunction "GND_3") (pintype "bidirectional"))
      (node (ref "JP5") (pin "5") (pinfunction "GND_5") (pintype "bidirectional"))
      (node (ref "R11") (pin "1") (pinfunction "1_1") (pintype "passive"))
      (node (ref "R15") (pin "1") (pinfunction "1_1") (pintype "passive"))
      (node (ref "R17") (pin "1") (pinfunction "1_1") (pintype "passive"))
      (node (ref "R2") (pin "1") (pinfunction "1_1") (pintype "passive"))
      (node (ref "R4") (pin "1") (pinfunction "1_1") (pintype "passive"))
      (node (ref "R6") (pin "1") (pinfunction "1_1") (pintype "passive"))
      (node (ref "S1") (pin "1") (pinfunction "1_1") (pintype "passive"))
      (node (ref "S1") (pin "2") (pinfunction "1_2") (pintype "passive"))
      (node (ref "S3") (pin "3") (pinfunction "2_3") (pintype "passive"))
      (node (ref "S3") (pin "4") (pinfunction "2_4") (pintype "passive"))
      (node (ref "U1") (pin "18") (pinfunction "GND_18") (pintype "bidirectional"))
      (node (ref "U1") (pin "35") (pinfunction "GND_35") (pintype "bidirectional"))
      (node (ref "U1") (pin "42") (pinfunction "GND_42") (pintype "bidirectional"))
      (node (ref "U1") (pin "5") (pinfunction "GNDANA_5") (pintype "bidirectional"))
      (node (ref "U2") (pin "2") (pinfunction "GND_2") (pintype "input"))
      (node (ref "U5") (pin "2") (pinfunction "V-_2") (pintype "power_in"))
      (node (ref "U6") (pin "2") (pinfunction "GND_2") (pintype "bidirectional"))
      (node (ref "U6") (pin "4") (pinfunction "GND_4") (pintype "bidirectional"))
      (node (ref "U6") (pin "6") (pinfunction "GND_6") (pintype "bidirectional"))
      (node (ref "U7") (pin "6") (pinfunction "GND_6") (pintype "bidirectional"))
    )
    (net (code "26") (name "ID") (class "Default")
      (node (ref "JP3") (pin "ID1") (pinfunction "USBID_ID1") (pintype "bidirectional"))
    )
    (net (code "27") (name "Net-(C19-Pad2)") (class "Default")
      (node (ref "C19") (pin "2") (pinfunction "2_2") (pintype "passive"))
      (node (ref "R12") (pin "2") (pinfunction "2_2") (pintype "passive"))
    )
    (net (code "28") (name "Net-(D1-PadC)") (class "Default")
      (node (ref "D1") (pin "C") (pinfunction "C_C") (pintype "passive"))
      (node (ref "R15") (pin "2") (pinfunction "2_2") (pintype "passive"))
    )
    (net (code "29") (name "Net-(D2-DO)") (class "Default")
      (node (ref "D2") (pin "2") (pinfunction "DO_2") (pintype "bidirectional"))
      (node (ref "D5") (pin "4") (pinfunction "DI_4") (pintype "bidirectional"))
    )
    (net (code "30") (name "Net-(D3-PadC)") (class "Default")
      (node (ref "D3") (pin "C") (pinfunction "C_C") (pintype "passive"))
      (node (ref "R17") (pin "2") (pinfunction "2_2") (pintype "passive"))
    )
    (net (code "31") (name "Net-(D4-PadC)") (class "Default")
      (node (ref "D4") (pin "C") (pinfunction "C_C") (pintype "passive"))
      (node (ref "R2") (pin "2") (pinfunction "2_2") (pintype "passive"))
    )
    (net (code "32") (name "Net-(D5-DO)") (class "Default")
      (node (ref "D5") (pin "2") (pinfunction "DO_2") (pintype "bidirectional"))
      (node (ref "D6") (pin "4") (pinfunction "DI_4") (pintype "bidirectional"))
    )
    (net (code "33") (name "Net-(D7-PadC)") (class "Default")
      (node (ref "D7") (pin "C") (pinfunction "C_C") (pintype "passive"))
      (node (ref "R6") (pin "2") (pinfunction "2_2") (pintype "passive"))
    )
    (net (code "34") (name "Net-(D31-DO)") (class "Default")
      (node (ref "D31") (pin "2") (pinfunction "DO_2") (pintype "bidirectional"))
      (node (ref "D32") (pin "4") (pinfunction "DI_4") (pintype "bidirectional"))
    )
    (net (code "35") (name "Net-(D32-DO)") (class "Default")
      (node (ref "D32") (pin "2") (pinfunction "DO_2") (pintype "bidirectional"))
      (node (ref "D33") (pin "4") (pinfunction "DI_4") (pintype "bidirectional"))
    )
    (net (code "36") (name "Net-(Q1-S)") (class "Default")
      (node (ref "D8") (pin "C") (pinfunction "C_C") (pintype "passive"))
      (node (ref "Q1") (pin "2") (pinfunction "S_2") (pintype "bidirectional"))
      (node (ref "S2") (pin "3") (pinfunction "S_3") (pintype "passive"))
    )
    (net (code "37") (name "Net-(U1-PA00(XIN32{slash}SER1:0{slash}TC2:0))") (class "Default")
      (node (ref "C5") (pin "2") (pinfunction "2_2") (pintype "passive"))
      (node (ref "U1") (pin "1") (pinfunction "PA00(XIN32/SER1:0/TC2:0)_1") (pintype "bidirectional"))
      (node (ref "Y1") (pin "P$2") (pinfunction "2_P$2") (pintype "passive"))
    )
    (net (code "38") (name "Net-(U1-PA01(XOUT32{slash}SER1:1{slash}TC2:1))") (class "Default")
      (node (ref "C6") (pin "1") (pinfunction "1_1") (pintype "passive"))
      (node (ref "U1") (pin "2") (pinfunction "PA01(XOUT32/SER1:1/TC2:1)_2") (pintype "bidirectional"))
      (node (ref "Y1") (pin "P$1") (pinfunction "1_P$1") (pintype "passive"))
    )
    (net (code "39") (name "Net-(U1-VDDCORE)") (class "Default")
      (node (ref "C2") (pin "1") (pinfunction "1_1") (pintype "passive"))
      (node (ref "U1") (pin "43") (pinfunction "VDDCORE_43") (pintype "bidirectional"))
    )
    (net (code "40") (name "Net-(U5-+IN)") (class "Default")
      (node (ref "C20") (pin "1") (pinfunction "1_1") (pintype "passive"))
      (node (ref "R11") (pin "2") (pinfunction "2_2") (pintype "passive"))
      (node (ref "R9") (pin "1") (pinfunction "1_1") (pintype "passive"))
      (node (ref "U5") (pin "3") (pinfunction "+IN_3") (pintype "input"))
    )
    (net (code "41") (name "Net-(U5--IN)") (class "Default")
      (node (ref "C17") (pin "1") (pinfunction "1_1") (pintype "passive"))
      (node (ref "R12") (pin "1") (pinfunction "1_1") (pintype "passive"))
      (node (ref "R13") (pin "2") (pinfunction "2_2") (pintype "passive"))
      (node (ref "U5") (pin "4") (pinfunction "-IN_4") (pintype "input"))
    )
    (net (code "42") (name "Net-(U6-OUT)") (class "Default")
      (node (ref "C19") (pin "1") (pinfunction "1_1") (pintype "passive"))
      (node (ref "U6") (pin "1") (pinfunction "OUT_1") (pintype "bidirectional"))
    )
    (net (code "43") (name "Net-(U7-LDR)") (class "Default")
      (node (ref "U7") (pin "3") (pinfunction "LDR_3") (pintype "bidirectional"))
      (node (ref "U7") (pin "4") (pinfunction "LEDK_4") (pintype "bidirectional"))
    )
    (net (code "44") (name "Net-(U7-LEDA)") (class "Default")
      (node (ref "C13") (pin "1") (pinfunction "1_1") (pintype "passive"))
      (node (ref "R29") (pin "1") (pinfunction "1_1") (pintype "passive"))
      (node (ref "U7") (pin "5") (pinfunction "LEDA_5") (pintype "bidirectional"))
    )
    (net (code "45") (name "SCL") (class "Default")
      (node (ref "J13") (pin "P$1") (pinfunction "1_P$1") (pintype "passive"))
      (node (ref "J15") (pin "P$1") (pinfunction "1_P$1") (pintype "passive"))
      (node (ref "J38") (pin "P$1") (pinfunction "1_P$1") (pintype "passive"))
      (node (ref "R5") (pin "2") (pinfunction "2_2") (pintype "passive"))
      (node (ref "U1") (pin "32") (pinfunction "PA23(I2C/SER3:0+)_32") (pintype "bidirectional"))
      (node (ref "U7") (pin "7") (pinfunction "SCL_7") (pintype "bidirectional"))
    )
    (net (code "46") (name "SDA") (class "Default")
      (node (ref "J12") (pin "P$1") (pinfunction "1_P$1") (pintype "passive"))
      (node (ref "J16") (pin "P$1") (pinfunction "1_P$1") (pintype "passive"))
      (node (ref "J39") (pin "P$1") (pinfunction "1_P$1") (pintype "passive"))
      (node (ref "R3") (pin "1") (pinfunction "1_1") (pintype "passive"))
      (node (ref "U1") (pin "31") (pinfunction "PA22(I2C/SER3:0+)_31") (pintype "bidirectional"))
      (node (ref "U7") (pin "1") (pinfunction "SDA_1") (pintype "bidirectional"))
    )
    (net (code "47") (name "SWCLK") (class "Default")
      (node (ref "JP5") (pin "4") (pinfunction "SWDCLK/TCK_4") (pintype "bidirectional"))
      (node (ref "U1") (pin "45") (pinfunction "PA30(SWCLK/SER1:2+)_45") (pintype "bidirectional"))
    )
    (net (code "48") (name "SWDIO") (class "Default")
      (node (ref "JP5") (pin "2") (pinfunction "SWDIO/TMS_2") (pintype "bidirectional"))
      (node (ref "U1") (pin "46") (pinfunction "PA31(SWDIO/SER1:3+)_46") (pintype "bidirectional"))
    )
    (net (code "49") (name "USB_D+") (class "Default")
      (node (ref "JP3") (pin "D+1") (pinfunction "D+_D+1") (pintype "bidirectional"))
      (node (ref "U1") (pin "34") (pinfunction "PA25(SER3:3+)_34") (pintype "bidirectional"))
    )
    (net (code "50") (name "USB_D-") (class "Default")
      (node (ref "JP3") (pin "D-1") (pinfunction "D-_D-1") (pintype "bidirectional"))
      (node (ref "U1") (pin "33") (pinfunction "PA24(SER3:2+)_33") (pintype "bidirectional"))
    )
    (net (code "51") (name "VIN") (class "Default")
      (node (ref "C9") (pin "1") (pinfunction "1_1") (pintype "passive"))
      (node (ref "J71") (pin "P$1") (pinfunction "1_P$1") (pintype "passive"))
      (node (ref "Q1") (pin "3") (pinfunction "D_3") (pintype "bidirectional"))
    )
    (net (code "52") (name "unconnected-(JP5-GNDDTCT-Pad9)") (class "Default")
      (node (ref "JP5") (pin "9") (pinfunction "GNDDTCT_9") (pintype "bidirectional"))
    )
    (net (code "53") (name "unconnected-(JP5-KEY-Pad7)") (class "Default")
      (node (ref "JP5") (pin "7") (pinfunction "KEY_7") (pintype "bidirectional"))
    )
    (net (code "54") (name "unconnected-(JP5-NC{slash}TDI-Pad8)") (class "Default")
      (node (ref "JP5") (pin "8") (pinfunction "NC/TDI_8") (pintype "bidirectional"))
    )
    (net (code "55") (name "unconnected-(JP5-SWO{slash}TDO-Pad6)") (class "Default")
      (node (ref "JP5") (pin "6") (pinfunction "SWO/TDO_6") (pintype "bidirectional"))
    )
    (net (code "56") (name "unconnected-(S2-O-Pad1)") (class "Default")
      (node (ref "S2") (pin "1") (pinfunction "O_1") (pintype "passive"))
    )
    (net (code "57") (name "unconnected-(U1-PA03(AIN1{slash}REFA)-Pad4)") (class "Default")
      (node (ref "U1") (pin "4") (pinfunction "PA03(AIN1/REFA)_4") (pintype "bidirectional"))
    )
    (net (code "58") (name "unconnected-(U1-PA05(AIN5{slash}SER0:1{slash}TC0:1)-Pad10)") (class "Default")
      (node (ref "U1") (pin "10") (pinfunction "PA05(AIN5/SER0:1/TC0:1)_10") (pintype "bidirectional"))
    )
    (net (code "59") (name "unconnected-(U1-PA12(I2C{slash}SER2:0+)-Pad21)") (class "Default")
      (node (ref "U1") (pin "21") (pinfunction "PA12(I2C/SER2:0+)_21") (pintype "bidirectional"))
    )
    (net (code "60") (name "unconnected-(U1-PA13(I2C{slash}SER2:1+)-Pad22)") (class "Default")
      (node (ref "U1") (pin "22") (pinfunction "PA13(I2C/SER2:1+)_22") (pintype "bidirectional"))
    )
    (net (code "61") (name "unconnected-(U1-PA27-Pad39)") (class "Default")
      (node (ref "U1") (pin "39") (pinfunction "PA27_39") (pintype "bidirectional"))
    )
    (net (code "62") (name "unconnected-(U1-PA28-Pad41)") (class "Default")
      (node (ref "U1") (pin "41") (pinfunction "PA28_41") (pintype "bidirectional"))
    )
    (net (code "63") (name "unconnected-(U1-PB02(AIN10{slash}SER5:0)-Pad47)") (class "Default")
      (node (ref "U1") (pin "47") (pinfunction "PB02(AIN10/SER5:0)_47") (pintype "bidirectional"))
    )
    (net (code "64") (name "unconnected-(U1-PB03(AIN11{slash}SER5:1)-Pad48)") (class "Default")
      (node (ref "U1") (pin "48") (pinfunction "PB03(AIN11/SER5:1)_48") (pintype "bidirectional"))
    )
    (net (code "65") (name "unconnected-(U1-PB10(SER4:2+)-Pad19)") (class "Default")
      (node (ref "U1") (pin "19") (pinfunction "PB10(SER4:2+)_19") (pintype "bidirectional"))
    )
    (net (code "66") (name "unconnected-(U1-PB11(SER4:3+)-Pad20)") (class "Default")
      (node (ref "U1") (pin "20") (pinfunction "PB11(SER4:3+)_20") (pintype "bidirectional"))
    )
    (net (code "67") (name "unconnected-(U1-PB22(SER5:2+)-Pad37)") (class "Default")
      (node (ref "U1") (pin "37") (pinfunction "PB22(SER5:2+)_37") (pintype "bidirectional"))
    )
    (net (code "68") (name "unconnected-(U1-PB23(SER5:3+)-Pad38)") (class "Default")
      (node (ref "U1") (pin "38") (pinfunction "PB23(SER5:3+)_38") (pintype "bidirectional"))
    )
    (net (code "69") (name "unconnected-(U2-NC-Pad4)") (class "Default")
      (node (ref "U2") (pin "4") (pinfunction "NC_4") (pintype "input"))
    )
    (net (code "70") (name "unconnected-(U7-INT-Pad2)") (class "Default")
      (node (ref "U7") (pin "2") (pinfunction "INT_2") (pintype "bidirectional"))
    )
  )
)
